# control_board_v2.net
KiCad netlist of a schematic drawn in EAGLE
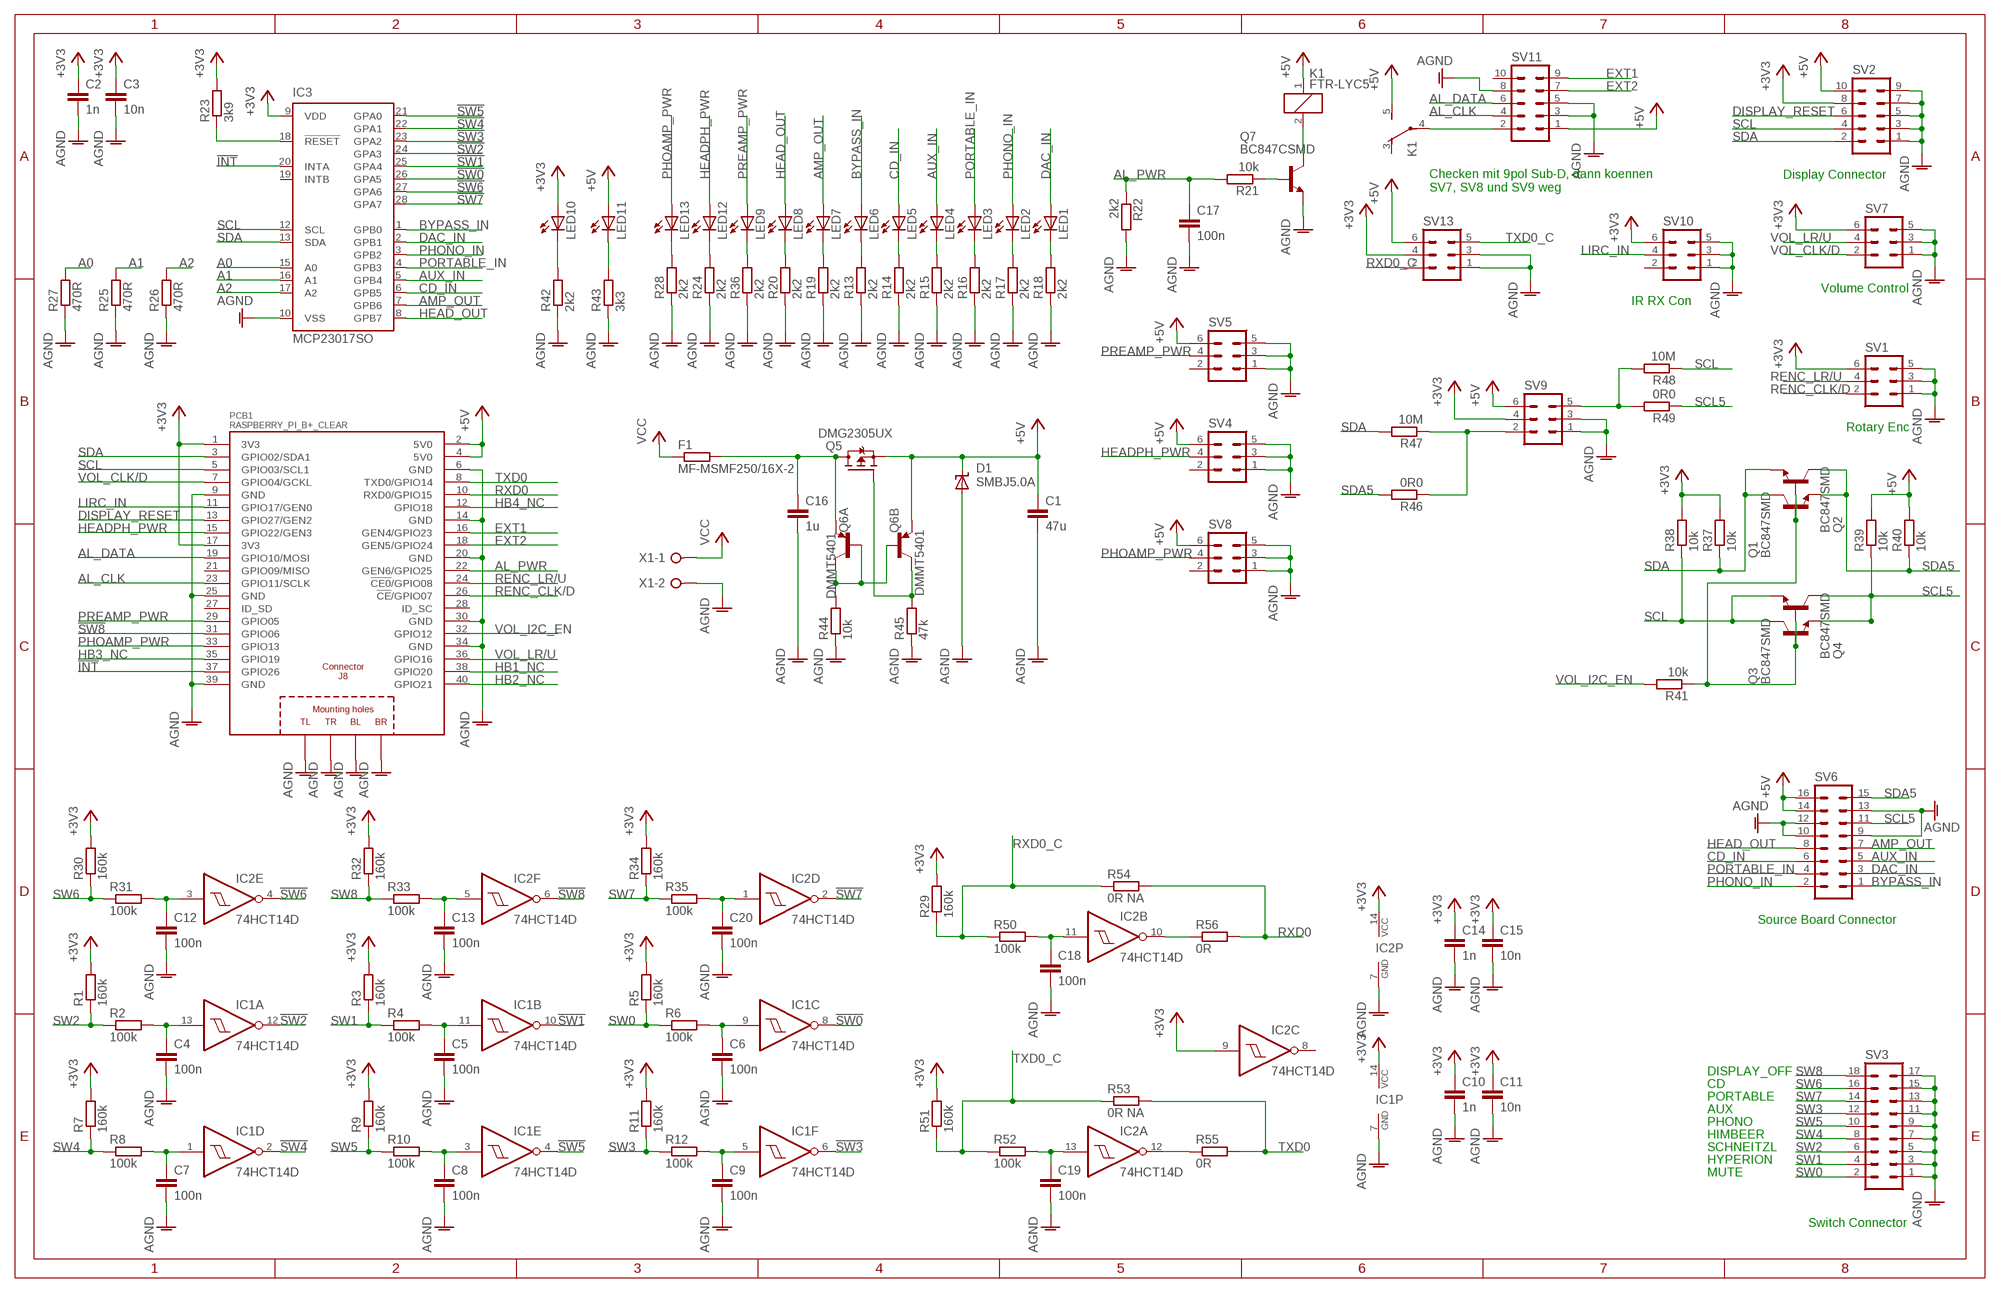
[diagram p0: schematic, sheet 1]

(export (version "E")
  (design (tool "Eeschema 10.0.6"))
  (components
    (comp (ref "C1")
      (value "47u")
      (footprint "eagle-import:C1812")
      (libsource (lib "eagle-import") (part "C-EUC1812"))
    )
    (comp (ref "C2")
      (value "1n")
      (footprint "eagle-import:C0603")
      (libsource (lib "eagle-import") (part "C-EUC0603"))
    )
    (comp (ref "C3")
      (value "10n")
      (footprint "eagle-import:C0603")
      (libsource (lib "eagle-import") (part "C-EUC0603"))
    )
    (comp (ref "C4")
      (value "100n")
      (footprint "eagle-import:C0603")
      (libsource (lib "eagle-import") (part "C-EUC0603"))
    )
    (comp (ref "C5")
      (value "100n")
      (footprint "eagle-import:C0603")
      (libsource (lib "eagle-import") (part "C-EUC0603"))
    )
    (comp (ref "C6")
      (value "100n")
      (footprint "eagle-import:C0603")
      (libsource (lib "eagle-import") (part "C-EUC0603"))
    )
    (comp (ref "C7")
      (value "100n")
      (footprint "eagle-import:C0603")
      (libsource (lib "eagle-import") (part "C-EUC0603"))
    )
    (comp (ref "C8")
      (value "100n")
      (footprint "eagle-import:C0603")
      (libsource (lib "eagle-import") (part "C-EUC0603"))
    )
    (comp (ref "C9")
      (value "100n")
      (footprint "eagle-import:C0603")
      (libsource (lib "eagle-import") (part "C-EUC0603"))
    )
    (comp (ref "C10")
      (value "1n")
      (footprint "eagle-import:C0603")
      (libsource (lib "eagle-import") (part "C-EUC0603"))
    )
    (comp (ref "C11")
      (value "10n")
      (footprint "eagle-import:C0603")
      (libsource (lib "eagle-import") (part "C-EUC0603"))
    )
    (comp (ref "C12")
      (value "100n")
      (footprint "eagle-import:C0603")
      (libsource (lib "eagle-import") (part "C-EUC0603"))
    )
    (comp (ref "C13")
      (value "100n")
      (footprint "eagle-import:C0603")
      (libsource (lib "eagle-import") (part "C-EUC0603"))
    )
    (comp (ref "C14")
      (value "1n")
      (footprint "eagle-import:C0603")
      (libsource (lib "eagle-import") (part "C-EUC0603"))
    )
    (comp (ref "C15")
      (value "10n")
      (footprint "eagle-import:C0603")
      (libsource (lib "eagle-import") (part "C-EUC0603"))
    )
    (comp (ref "C16")
      (value "1u")
      (footprint "eagle-import:C1206")
      (libsource (lib "eagle-import") (part "C-EUC1206"))
    )
    (comp (ref "C17")
      (value "100n")
      (footprint "eagle-import:C0603")
      (libsource (lib "eagle-import") (part "C-EUC0603"))
    )
    (comp (ref "C18")
      (value "100n")
      (footprint "eagle-import:C0603")
      (libsource (lib "eagle-import") (part "C-EUC0603"))
    )
    (comp (ref "C19")
      (value "100n")
      (footprint "eagle-import:C0603")
      (libsource (lib "eagle-import") (part "C-EUC0603"))
    )
    (comp (ref "C20")
      (value "100n")
      (footprint "eagle-import:C0603")
      (libsource (lib "eagle-import") (part "C-EUC0603"))
    )
    (comp (ref "D1")
      (value "SMBJ5.0A")
      (footprint "eagle-import:SMBJ")
      (libsource (lib "eagle-import") (part "SMBJ5.0A"))
    )
    (comp (ref "F1")
      (value "MF-MSMF250/16X-2")
      (footprint "eagle-import:1812X7R")
      (libsource (lib "eagle-import") (part "R-EU_1812X7R"))
    )
    (comp (ref "IC1")
      (value "74HCT14D")
      (footprint "eagle-import:SO14")
      (libsource (lib "eagle-import") (part "7414DHCT"))
    )
    (comp (ref "IC2")
      (value "74HCT14D")
      (footprint "eagle-import:SO14")
      (libsource (lib "eagle-import") (part "7414DHCT"))
    )
    (comp (ref "IC3")
      (value "MCP23017SO")
      (footprint "eagle-import:SO28W")
      (fields (field (name "MF") "MICROCHIP") (field (name "MPN") "MCP23017-E/SO"))
      (libsource (lib "eagle-import") (part "MCP23017SO"))
    )
    (comp (ref "K1")
      (value "FTR-LYC5")
      (footprint "eagle-import:FTR-LYC")
      (libsource (lib "eagle-import") (part "FTR-LYC5"))
    )
    (comp (ref "LED1")
      (value "LEDCHIPLED_0603")
      (footprint "eagle-import:CHIPLED_0603")
      (libsource (lib "eagle-import") (part "LEDCHIPLED_0603"))
    )
    (comp (ref "LED2")
      (value "LEDCHIPLED_0603")
      (footprint "eagle-import:CHIPLED_0603")
      (libsource (lib "eagle-import") (part "LEDCHIPLED_0603"))
    )
    (comp (ref "LED3")
      (value "LEDCHIPLED_0603")
      (footprint "eagle-import:CHIPLED_0603")
      (libsource (lib "eagle-import") (part "LEDCHIPLED_0603"))
    )
    (comp (ref "LED4")
      (value "LEDCHIPLED_0603")
      (footprint "eagle-import:CHIPLED_0603")
      (libsource (lib "eagle-import") (part "LEDCHIPLED_0603"))
    )
    (comp (ref "LED5")
      (value "LEDCHIPLED_0603")
      (footprint "eagle-import:CHIPLED_0603")
      (libsource (lib "eagle-import") (part "LEDCHIPLED_0603"))
    )
    (comp (ref "LED6")
      (value "LEDCHIPLED_0603")
      (footprint "eagle-import:CHIPLED_0603")
      (libsource (lib "eagle-import") (part "LEDCHIPLED_0603"))
    )
    (comp (ref "LED7")
      (value "LEDCHIPLED_0603")
      (footprint "eagle-import:CHIPLED_0603")
      (libsource (lib "eagle-import") (part "LEDCHIPLED_0603"))
    )
    (comp (ref "LED8")
      (value "LEDCHIPLED_0603")
      (footprint "eagle-import:CHIPLED_0603")
      (libsource (lib "eagle-import") (part "LEDCHIPLED_0603"))
    )
    (comp (ref "LED9")
      (value "LEDCHIPLED_0603")
      (footprint "eagle-import:CHIPLED_0603")
      (libsource (lib "eagle-import") (part "LEDCHIPLED_0603"))
    )
    (comp (ref "LED10")
      (value "LEDCHIPLED_0603")
      (footprint "eagle-import:CHIPLED_0603")
      (libsource (lib "eagle-import") (part "LEDCHIPLED_0603"))
    )
    (comp (ref "LED11")
      (value "LEDCHIPLED_0603")
      (footprint "eagle-import:CHIPLED_0603")
      (libsource (lib "eagle-import") (part "LEDCHIPLED_0603"))
    )
    (comp (ref "LED12")
      (value "LEDCHIPLED_0603")
      (footprint "eagle-import:CHIPLED_0603")
      (libsource (lib "eagle-import") (part "LEDCHIPLED_0603"))
    )
    (comp (ref "LED13")
      (value "LEDCHIPLED_0603")
      (footprint "eagle-import:CHIPLED_0603")
      (libsource (lib "eagle-import") (part "LEDCHIPLED_0603"))
    )
    (comp (ref "PCB1")
      (value "RASPBERRY_PI_B+_CLEAR")
      (footprint "eagle-import:RASPBERRY_PI_PLUS_CLEAR")
      (libsource (lib "eagle-import") (part "RASPBERRY_PI_B+_CLEAR"))
    )
    (comp (ref "Q1")
      (value "BC847SMD")
      (footprint "eagle-import:SOT23")
      (libsource (lib "eagle-import") (part "BC847SMD"))
    )
    (comp (ref "Q2")
      (value "BC847SMD")
      (footprint "eagle-import:SOT23")
      (libsource (lib "eagle-import") (part "BC847SMD"))
    )
    (comp (ref "Q3")
      (value "BC847SMD")
      (footprint "eagle-import:SOT23")
      (libsource (lib "eagle-import") (part "BC847SMD"))
    )
    (comp (ref "Q4")
      (value "BC847SMD")
      (footprint "eagle-import:SOT23")
      (libsource (lib "eagle-import") (part "BC847SMD"))
    )
    (comp (ref "Q5")
      (value "DMG2305UX")
      (footprint "eagle-import:SOT23")
      (libsource (lib "eagle-import") (part "DMG2305UX"))
    )
    (comp (ref "Q6")
      (value "DMMT5401")
      (footprint "eagle-import:SOT23-6")
      (libsource (lib "eagle-import") (part "DMMT5401"))
    )
    (comp (ref "Q7")
      (value "BC847CSMD")
      (footprint "eagle-import:SOT23")
      (libsource (lib "eagle-import") (part "BC847SMDC"))
    )
    (comp (ref "R1")
      (value "160k")
      (footprint "eagle-import:R0603")
      (libsource (lib "eagle-import") (part "R-EU_R0603"))
    )
    (comp (ref "R2")
      (value "100k")
      (footprint "eagle-import:R0603")
      (libsource (lib "eagle-import") (part "R-EU_R0603"))
    )
    (comp (ref "R3")
      (value "160k")
      (footprint "eagle-import:R0603")
      (libsource (lib "eagle-import") (part "R-EU_R0603"))
    )
    (comp (ref "R4")
      (value "100k")
      (footprint "eagle-import:R0603")
      (libsource (lib "eagle-import") (part "R-EU_R0603"))
    )
    (comp (ref "R5")
      (value "160k")
      (footprint "eagle-import:R0603")
      (libsource (lib "eagle-import") (part "R-EU_R0603"))
    )
    (comp (ref "R6")
      (value "100k")
      (footprint "eagle-import:R0603")
      (libsource (lib "eagle-import") (part "R-EU_R0603"))
    )
    (comp (ref "R7")
      (value "160k")
      (footprint "eagle-import:R0603")
      (libsource (lib "eagle-import") (part "R-EU_R0603"))
    )
    (comp (ref "R8")
      (value "100k")
      (footprint "eagle-import:R0603")
      (libsource (lib "eagle-import") (part "R-EU_R0603"))
    )
    (comp (ref "R9")
      (value "160k")
      (footprint "eagle-import:R0603")
      (libsource (lib "eagle-import") (part "R-EU_R0603"))
    )
    (comp (ref "R10")
      (value "100k")
      (footprint "eagle-import:R0603")
      (libsource (lib "eagle-import") (part "R-EU_R0603"))
    )
    (comp (ref "R11")
      (value "160k")
      (footprint "eagle-import:R0603")
      (libsource (lib "eagle-import") (part "R-EU_R0603"))
    )
    (comp (ref "R12")
      (value "100k")
      (footprint "eagle-import:R0603")
      (libsource (lib "eagle-import") (part "R-EU_R0603"))
    )
    (comp (ref "R13")
      (value "2k2")
      (footprint "eagle-import:R0603")
      (libsource (lib "eagle-import") (part "R-EU_R0603"))
    )
    (comp (ref "R14")
      (value "2k2")
      (footprint "eagle-import:R0603")
      (libsource (lib "eagle-import") (part "R-EU_R0603"))
    )
    (comp (ref "R15")
      (value "2k2")
      (footprint "eagle-import:R0603")
      (libsource (lib "eagle-import") (part "R-EU_R0603"))
    )
    (comp (ref "R16")
      (value "2k2")
      (footprint "eagle-import:R0603")
      (libsource (lib "eagle-import") (part "R-EU_R0603"))
    )
    (comp (ref "R17")
      (value "2k2")
      (footprint "eagle-import:R0603")
      (libsource (lib "eagle-import") (part "R-EU_R0603"))
    )
    (comp (ref "R18")
      (value "2k2")
      (footprint "eagle-import:R0603")
      (libsource (lib "eagle-import") (part "R-EU_R0603"))
    )
    (comp (ref "R19")
      (value "2k2")
      (footprint "eagle-import:R0603")
      (libsource (lib "eagle-import") (part "R-EU_R0603"))
    )
    (comp (ref "R20")
      (value "2k2")
      (footprint "eagle-import:R0603")
      (libsource (lib "eagle-import") (part "R-EU_R0603"))
    )
    (comp (ref "R21")
      (value "10k")
      (footprint "eagle-import:R0603")
      (libsource (lib "eagle-import") (part "R-EU_R0603"))
    )
    (comp (ref "R22")
      (value "2k2")
      (footprint "eagle-import:R0603")
      (libsource (lib "eagle-import") (part "R-EU_R0603"))
    )
    (comp (ref "R23")
      (value "3k9")
      (footprint "eagle-import:R1206")
      (libsource (lib "eagle-import") (part "R-EU_R1206"))
    )
    (comp (ref "R24")
      (value "2k2")
      (footprint "eagle-import:R0603")
      (libsource (lib "eagle-import") (part "R-EU_R0603"))
    )
    (comp (ref "R25")
      (value "470R")
      (footprint "eagle-import:R0603")
      (libsource (lib "eagle-import") (part "R-EU_R0603"))
    )
    (comp (ref "R26")
      (value "470R")
      (footprint "eagle-import:R0603")
      (libsource (lib "eagle-import") (part "R-EU_R0603"))
    )
    (comp (ref "R27")
      (value "470R")
      (footprint "eagle-import:R0603")
      (libsource (lib "eagle-import") (part "R-EU_R0603"))
    )
    (comp (ref "R28")
      (value "2k2")
      (footprint "eagle-import:R0603")
      (libsource (lib "eagle-import") (part "R-EU_R0603"))
    )
    (comp (ref "R29")
      (value "160k")
      (footprint "eagle-import:R0603")
      (libsource (lib "eagle-import") (part "R-EU_R0603"))
    )
    (comp (ref "R30")
      (value "160k")
      (footprint "eagle-import:R0603")
      (libsource (lib "eagle-import") (part "R-EU_R0603"))
    )
    (comp (ref "R31")
      (value "100k")
      (footprint "eagle-import:R0603")
      (libsource (lib "eagle-import") (part "R-EU_R0603"))
    )
    (comp (ref "R32")
      (value "160k")
      (footprint "eagle-import:R0603")
      (libsource (lib "eagle-import") (part "R-EU_R0603"))
    )
    (comp (ref "R33")
      (value "100k")
      (footprint "eagle-import:R0603")
      (libsource (lib "eagle-import") (part "R-EU_R0603"))
    )
    (comp (ref "R34")
      (value "160k")
      (footprint "eagle-import:R0603")
      (libsource (lib "eagle-import") (part "R-EU_R0603"))
    )
    (comp (ref "R35")
      (value "100k")
      (footprint "eagle-import:R0603")
      (libsource (lib "eagle-import") (part "R-EU_R0603"))
    )
    (comp (ref "R36")
      (value "2k2")
      (footprint "eagle-import:R0603")
      (libsource (lib "eagle-import") (part "R-EU_R0603"))
    )
    (comp (ref "R37")
      (value "10k")
      (footprint "eagle-import:R1206")
      (libsource (lib "eagle-import") (part "resistor_R-EU_R1206"))
    )
    (comp (ref "R38")
      (value "10k")
      (footprint "eagle-import:R0603")
      (libsource (lib "eagle-import") (part "resistor_R-EU_R0603"))
    )
    (comp (ref "R39")
      (value "10k")
      (footprint "eagle-import:R0603")
      (libsource (lib "eagle-import") (part "resistor_R-EU_R0603"))
    )
    (comp (ref "R40")
      (value "10k")
      (footprint "eagle-import:R0603")
      (libsource (lib "eagle-import") (part "R-EU_R0603"))
    )
    (comp (ref "R41")
      (value "10k")
      (footprint "eagle-import:R1206")
      (libsource (lib "eagle-import") (part "resistor_R-EU_R1206"))
    )
    (comp (ref "R42")
      (value "2k2")
      (footprint "eagle-import:R0603")
      (libsource (lib "eagle-import") (part "R-EU_R0603"))
    )
    (comp (ref "R43")
      (value "3k3")
      (footprint "eagle-import:R0603")
      (libsource (lib "eagle-import") (part "R-EU_R0603"))
    )
    (comp (ref "R44")
      (value "10k")
      (footprint "eagle-import:R0603")
      (libsource (lib "eagle-import") (part "R-EU_R0603"))
    )
    (comp (ref "R45")
      (value "47k")
      (footprint "eagle-import:R0603")
      (libsource (lib "eagle-import") (part "R-EU_R0603"))
    )
    (comp (ref "R46")
      (value "0R0")
      (footprint "eagle-import:R0603")
      (libsource (lib "eagle-import") (part "R-EU_R0603"))
    )
    (comp (ref "R47")
      (value "10M")
      (footprint "eagle-import:R0603")
      (libsource (lib "eagle-import") (part "R-EU_R0603"))
    )
    (comp (ref "R48")
      (value "10M")
      (footprint "eagle-import:R0603")
      (libsource (lib "eagle-import") (part "R-EU_R0603"))
    )
    (comp (ref "R49")
      (value "0R0")
      (footprint "eagle-import:R0603")
      (libsource (lib "eagle-import") (part "R-EU_R0603"))
    )
    (comp (ref "R50")
      (value "100k")
      (footprint "eagle-import:R0603")
      (libsource (lib "eagle-import") (part "R-EU_R0603"))
    )
    (comp (ref "R51")
      (value "160k")
      (footprint "eagle-import:R0603")
      (libsource (lib "eagle-import") (part "R-EU_R0603"))
    )
    (comp (ref "R52")
      (value "100k")
      (footprint "eagle-import:R0603")
      (libsource (lib "eagle-import") (part "R-EU_R0603"))
    )
    (comp (ref "R53")
      (value "0R NA")
      (footprint "eagle-import:R0603")
      (libsource (lib "eagle-import") (part "R-EU_R0603"))
    )
    (comp (ref "R54")
      (value "0R NA")
      (footprint "eagle-import:R0603")
      (libsource (lib "eagle-import") (part "R-EU_R0603"))
    )
    (comp (ref "R55")
      (value "0R")
      (footprint "eagle-import:R0603")
      (libsource (lib "eagle-import") (part "R-EU_R0603"))
    )
    (comp (ref "R56")
      (value "0R")
      (footprint "eagle-import:R0603")
      (libsource (lib "eagle-import") (part "R-EU_R0603"))
    )
    (comp (ref "SV1")
      (value "MA03-2B")
      (footprint "eagle-import:MA03-2_BORDER")
      (libsource (lib "eagle-import") (part "MA03-2B"))
    )
    (comp (ref "SV2")
      (value "MA05-2B")
      (footprint "eagle-import:MA05-2_BORDER")
      (libsource (lib "eagle-import") (part "MA05-2B"))
    )
    (comp (ref "SV3")
      (value "MA09-2B")
      (footprint "eagle-import:MA09-2_BORDER")
      (libsource (lib "eagle-import") (part "MA09-2B"))
    )
    (comp (ref "SV4")
      (value "MA03-2B")
      (footprint "eagle-import:MA03-2_BORDER")
      (libsource (lib "eagle-import") (part "MA03-2B"))
    )
    (comp (ref "SV5")
      (value "MA03-2B")
      (footprint "eagle-import:MA03-2_BORDER")
      (libsource (lib "eagle-import") (part "MA03-2B"))
    )
    (comp (ref "SV6")
      (value "MA08-2B")
      (footprint "eagle-import:MA08-2_BORDER")
      (libsource (lib "eagle-import") (part "MA08-2B"))
    )
    (comp (ref "SV7")
      (value "MA03-2B")
      (footprint "eagle-import:MA03-2_BORDER")
      (libsource (lib "eagle-import") (part "MA03-2B"))
    )
    (comp (ref "SV8")
      (value "MA03-2B")
      (footprint "eagle-import:MA03-2_BORDER")
      (libsource (lib "eagle-import") (part "MA03-2B"))
    )
    (comp (ref "SV9")
      (value "MA03-2B")
      (footprint "eagle-import:MA03-2_BORDER")
      (libsource (lib "eagle-import") (part "MA03-2B"))
    )
    (comp (ref "SV10")
      (value "MA03-2B")
      (footprint "eagle-import:MA03-2_BORDER")
      (libsource (lib "eagle-import") (part "MA03-2B"))
    )
    (comp (ref "SV11")
      (value "MA05-2B")
      (footprint "eagle-import:MA05-2_BORDER")
      (libsource (lib "eagle-import") (part "MA05-2B"))
    )
    (comp (ref "SV13")
      (value "MA03-2B")
      (footprint "eagle-import:MA03-2_BORDER")
      (libsource (lib "eagle-import") (part "MA03-2B"))
    )
    (comp (ref "X1")
      (value "W237-02P")
      (footprint "eagle-import:W237-132")
      (libsource (lib "eagle-import") (part "W237-02P"))
    )
  )
  (nets
    (net (code "1") (name "+3V3") (class "Default")
      (node (ref "C10") (pin "1") (pinfunction "1_1") (pintype "passive"))
      (node (ref "C11") (pin "1") (pinfunction "1_1") (pintype "passive"))
      (node (ref "C14") (pin "1") (pinfunction "1_1") (pintype "passive"))
      (node (ref "C15") (pin "1") (pinfunction "1_1") (pintype "passive"))
      (node (ref "C2") (pin "1") (pinfunction "1_1") (pintype "passive"))
      (node (ref "C3") (pin "1") (pinfunction "1_1") (pintype "passive"))
      (node (ref "IC1") (pin "14") (pinfunction "VCC_14") (pintype "power_in"))
      (node (ref "IC2") (pin "14") (pinfunction "VCC_14") (pintype "power_in"))
      (node (ref "IC2") (pin "9") (pinfunction "I_9") (pintype "input"))
      (node (ref "IC3") (pin "9") (pinfunction "VDD_9") (pintype "power_in"))
      (node (ref "LED10") (pin "A") (pinfunction "A_A") (pintype "passive"))
      (node (ref "PCB1") (pin "1") (pinfunction "3V3_1") (pintype "power_in"))
      (node (ref "PCB1") (pin "17") (pinfunction "3V3_17") (pintype "power_in"))
      (node (ref "R1") (pin "2") (pinfunction "2_2") (pintype "passive"))
      (node (ref "R11") (pin "2") (pinfunction "2_2") (pintype "passive"))
      (node (ref "R23") (pin "2") (pinfunction "2_2") (pintype "passive"))
      (node (ref "R29") (pin "2") (pinfunction "2_2") (pintype "passive"))
      (node (ref "R3") (pin "2") (pinfunction "2_2") (pintype "passive"))
      (node (ref "R30") (pin "2") (pinfunction "2_2") (pintype "passive"))
      (node (ref "R32") (pin "2") (pinfunction "2_2") (pintype "passive"))
      (node (ref "R34") (pin "2") (pinfunction "2_2") (pintype "passive"))
      (node (ref "R37") (pin "2") (pinfunction "2_2") (pintype "passive"))
      (node (ref "R38") (pin "2") (pinfunction "2_2") (pintype "passive"))
      (node (ref "R5") (pin "2") (pinfunction "2_2") (pintype "passive"))
      (node (ref "R51") (pin "2") (pinfunction "2_2") (pintype "passive"))
      (node (ref "R7") (pin "2") (pinfunction "2_2") (pintype "passive"))
      (node (ref "R9") (pin "2") (pinfunction "2_2") (pintype "passive"))
      (node (ref "SV1") (pin "6") (pinfunction "6_6") (pintype "passive"))
      (node (ref "SV10") (pin "6") (pinfunction "6_6") (pintype "passive"))
      (node (ref "SV13") (pin "4") (pinfunction "4_4") (pintype "passive"))
      (node (ref "SV2") (pin "8") (pinfunction "8_8") (pintype "passive"))
      (node (ref "SV7") (pin "6") (pinfunction "6_6") (pintype "passive"))
      (node (ref "SV9") (pin "4") (pinfunction "4_4") (pintype "passive"))
    )
    (net (code "2") (name "+5V") (class "Default")
      (node (ref "C1") (pin "1") (pinfunction "1_1") (pintype "passive"))
      (node (ref "D1") (pin "C") (pinfunction "C_C") (pintype "passive"))
      (node (ref "K1") (pin "1") (pinfunction "1_1") (pintype "passive"))
      (node (ref "K1") (pin "5") (pinfunction "S_5") (pintype "passive"))
      (node (ref "LED11") (pin "A") (pinfunction "A_A") (pintype "passive"))
      (node (ref "PCB1") (pin "2") (pinfunction "5V0_2") (pintype "power_in"))
      (node (ref "PCB1") (pin "4") (pinfunction "5V0_4") (pintype "power_in"))
      (node (ref "Q5") (pin "2") (pinfunction "S_2") (pintype "passive"))
      (node (ref "Q6") (pin "5") (pinfunction "E_5") (pintype "passive"))
      (node (ref "R39") (pin "2") (pinfunction "2_2") (pintype "passive"))
      (node (ref "R40") (pin "2") (pinfunction "2_2") (pintype "passive"))
      (node (ref "SV11") (pin "1") (pinfunction "1_1") (pintype "passive"))
      (node (ref "SV13") (pin "6") (pinfunction "6_6") (pintype "passive"))
      (node (ref "SV2") (pin "10") (pinfunction "10_10") (pintype "passive"))
      (node (ref "SV4") (pin "6") (pinfunction "6_6") (pintype "passive"))
      (node (ref "SV5") (pin "6") (pinfunction "6_6") (pintype "passive"))
      (node (ref "SV6") (pin "14") (pinfunction "14_14") (pintype "passive"))
      (node (ref "SV6") (pin "16") (pinfunction "16_16") (pintype "passive"))
      (node (ref "SV8") (pin "6") (pinfunction "6_6") (pintype "passive"))
      (node (ref "SV9") (pin "6") (pinfunction "6_6") (pintype "passive"))
    )
    (net (code "3") (name "/A0") (class "Default")
      (node (ref "IC3") (pin "15") (pinfunction "A0_15") (pintype "input"))
      (node (ref "R27") (pin "2") (pinfunction "2_2") (pintype "passive"))
    )
    (net (code "4") (name "/A1") (class "Default")
      (node (ref "IC3") (pin "16") (pinfunction "A1_16") (pintype "input"))
      (node (ref "R25") (pin "2") (pinfunction "2_2") (pintype "passive"))
    )
    (net (code "5") (name "/A2") (class "Default")
      (node (ref "IC3") (pin "17") (pinfunction "A2_17") (pintype "input"))
      (node (ref "R26") (pin "2") (pinfunction "2_2") (pintype "passive"))
    )
    (net (code "6") (name "/AL_CLK") (class "Default")
      (node (ref "PCB1") (pin "23") (pinfunction "GPIO11/SCLK_23") (pintype "bidirectional"))
      (node (ref "SV11") (pin "4") (pinfunction "4_4") (pintype "passive"))
    )
    (net (code "7") (name "/AL_DATA") (class "Default")
      (node (ref "PCB1") (pin "19") (pinfunction "GPIO10/MOSI_19") (pintype "bidirectional"))
      (node (ref "SV11") (pin "6") (pinfunction "6_6") (pintype "passive"))
    )
    (net (code "8") (name "/AL_PWR") (class "Default")
      (node (ref "C17") (pin "1") (pinfunction "1_1") (pintype "passive"))
      (node (ref "PCB1") (pin "22") (pinfunction "GEN6/GPIO25_22") (pintype "bidirectional"))
      (node (ref "R21") (pin "2") (pinfunction "2_2") (pintype "passive"))
      (node (ref "R22") (pin "1") (pinfunction "1_1") (pintype "passive"))
    )
    (net (code "9") (name "/AMP_OUT") (class "Default")
      (node (ref "IC3") (pin "7") (pinfunction "GPB6_7") (pintype "bidirectional"))
      (node (ref "LED7") (pin "A") (pinfunction "A_A") (pintype "passive"))
      (node (ref "SV6") (pin "7") (pinfunction "7_7") (pintype "passive"))
    )
    (net (code "10") (name "/AUX_IN") (class "Default")
      (node (ref "IC3") (pin "5") (pinfunction "GPB4_5") (pintype "bidirectional"))
      (node (ref "LED4") (pin "A") (pinfunction "A_A") (pintype "passive"))
      (node (ref "SV6") (pin "5") (pinfunction "5_5") (pintype "passive"))
    )
    (net (code "11") (name "/BYPASS_IN") (class "Default")
      (node (ref "IC3") (pin "1") (pinfunction "GPB0_1") (pintype "bidirectional"))
      (node (ref "LED6") (pin "A") (pinfunction "A_A") (pintype "passive"))
      (node (ref "SV6") (pin "1") (pinfunction "1_1") (pintype "passive"))
    )
    (net (code "12") (name "/CD_IN") (class "Default")
      (node (ref "IC3") (pin "6") (pinfunction "GPB5_6") (pintype "bidirectional"))
      (node (ref "LED5") (pin "A") (pinfunction "A_A") (pintype "passive"))
      (node (ref "SV6") (pin "6") (pinfunction "6_6") (pintype "passive"))
    )
    (net (code "13") (name "/DAC_IN") (class "Default")
      (node (ref "IC3") (pin "2") (pinfunction "GPB1_2") (pintype "bidirectional"))
      (node (ref "LED1") (pin "A") (pinfunction "A_A") (pintype "passive"))
      (node (ref "SV6") (pin "3") (pinfunction "3_3") (pintype "passive"))
    )
    (net (code "14") (name "/DISPLAY_RESET") (class "Default")
      (node (ref "PCB1") (pin "13") (pinfunction "GPIO27/GEN2_13") (pintype "bidirectional"))
      (node (ref "SV2") (pin "6") (pinfunction "6_6") (pintype "passive"))
    )
    (net (code "15") (name "/EXT1") (class "Default")
      (node (ref "PCB1") (pin "16") (pinfunction "GEN4/GPIO23_16") (pintype "bidirectional"))
      (node (ref "SV11") (pin "9") (pinfunction "9_9") (pintype "passive"))
    )
    (net (code "16") (name "/EXT2") (class "Default")
      (node (ref "PCB1") (pin "18") (pinfunction "GEN5/GPIO24_18") (pintype "bidirectional"))
      (node (ref "SV11") (pin "7") (pinfunction "7_7") (pintype "passive"))
    )
    (net (code "17") (name "/HB1_NC") (class "Default")
      (node (ref "PCB1") (pin "38") (pinfunction "GPIO20_38") (pintype "bidirectional"))
    )
    (net (code "18") (name "/HB2_NC") (class "Default")
      (node (ref "PCB1") (pin "40") (pinfunction "GPIO21_40") (pintype "bidirectional"))
    )
    (net (code "19") (name "/HB3_NC") (class "Default")
      (node (ref "PCB1") (pin "35") (pinfunction "GPIO19_35") (pintype "bidirectional"))
    )
    (net (code "20") (name "/HB4_NC") (class "Default")
      (node (ref "PCB1") (pin "12") (pinfunction "GPIO18_12") (pintype "bidirectional"))
    )
    (net (code "21") (name "/HEADPH_PWR") (class "Default")
      (node (ref "LED12") (pin "A") (pinfunction "A_A") (pintype "passive"))
      (node (ref "PCB1") (pin "15") (pinfunction "GPIO22/GEN3_15") (pintype "bidirectional"))
      (node (ref "SV4") (pin "4") (pinfunction "4_4") (pintype "passive"))
    )
    (net (code "22") (name "/HEAD_OUT") (class "Default")
      (node (ref "IC3") (pin "8") (pinfunction "GPB7_8") (pintype "bidirectional"))
      (node (ref "LED8") (pin "A") (pinfunction "A_A") (pintype "passive"))
      (node (ref "SV6") (pin "8") (pinfunction "8_8") (pintype "passive"))
    )
    (net (code "23") (name "/LIRC_IN") (class "Default")
      (node (ref "PCB1") (pin "11") (pinfunction "GPIO17/GEN0_11") (pintype "bidirectional"))
      (node (ref "SV10") (pin "4") (pinfunction "4_4") (pintype "passive"))
    )
    (net (code "24") (name "/PHOAMP_PWR") (class "Default")
      (node (ref "LED13") (pin "A") (pinfunction "A_A") (pintype "passive"))
      (node (ref "PCB1") (pin "33") (pinfunction "GPIO13_33") (pintype "bidirectional"))
      (node (ref "SV8") (pin "4") (pinfunction "4_4") (pintype "passive"))
    )
    (net (code "25") (name "/PHONO_IN") (class "Default")
      (node (ref "IC3") (pin "3") (pinfunction "GPB2_3") (pintype "bidirectional"))
      (node (ref "LED2") (pin "A") (pinfunction "A_A") (pintype "passive"))
      (node (ref "SV6") (pin "2") (pinfunction "2_2") (pintype "passive"))
    )
    (net (code "26") (name "/PORTABLE_IN") (class "Default")
      (node (ref "IC3") (pin "4") (pinfunction "GPB3_4") (pintype "bidirectional"))
      (node (ref "LED3") (pin "A") (pinfunction "A_A") (pintype "passive"))
      (node (ref "SV6") (pin "4") (pinfunction "4_4") (pintype "passive"))
    )
    (net (code "27") (name "/PREAMP_PWR") (class "Default")
      (node (ref "LED9") (pin "A") (pinfunction "A_A") (pintype "passive"))
      (node (ref "PCB1") (pin "29") (pinfunction "GPIO05_29") (pintype "bidirectional"))
      (node (ref "SV5") (pin "4") (pinfunction "4_4") (pintype "passive"))
    )
    (net (code "28") (name "/RENC_CLK{slash}D") (class "Default")
      (node (ref "PCB1") (pin "26") (pinfunction "~{CE}/GPIO07_26") (pintype "bidirectional"))
      (node (ref "SV1") (pin "2") (pinfunction "2_2") (pintype "passive"))
    )
    (net (code "29") (name "/RENC_LR{slash}U") (class "Default")
      (node (ref "PCB1") (pin "24") (pinfunction "~{CE0}/GPIO08_24") (pintype "bidirectional"))
      (node (ref "SV1") (pin "4") (pinfunction "4_4") (pintype "passive"))
    )
    (net (code "30") (name "/RXD0") (class "Default")
      (node (ref "PCB1") (pin "10") (pinfunction "RXD0/GPIO15_10") (pintype "bidirectional"))
      (node (ref "R54") (pin "2") (pinfunction "2_2") (pintype "passive"))
      (node (ref "R56") (pin "2") (pinfunction "2_2") (pintype "passive"))
    )
    (net (code "31") (name "/RXD0_C") (class "Default")
      (node (ref "R29") (pin "1") (pinfunction "1_1") (pintype "passive"))
      (node (ref "R50") (pin "1") (pinfunction "1_1") (pintype "passive"))
      (node (ref "R54") (pin "1") (pinfunction "1_1") (pintype "passive"))
      (node (ref "SV13") (pin "2") (pinfunction "2_2") (pintype "passive"))
    )
    (net (code "32") (name "/SCL") (class "Default")
      (node (ref "IC3") (pin "12") (pinfunction "SCL_12") (pintype "input"))
      (node (ref "PCB1") (pin "5") (pinfunction "GPIO03/SCL1_5") (pintype "bidirectional"))
      (node (ref "Q3") (pin "3") (pinfunction "C_3") (pintype "passive"))
      (node (ref "Q4") (pin "2") (pinfunction "E_2") (pintype "passive"))
      (node (ref "R38") (pin "1") (pinfunction "1_1") (pintype "passive"))
      (node (ref "R48") (pin "1") (pinfunction "1_1") (pintype "passive"))
      (node (ref "SV2") (pin "4") (pinfunction "4_4") (pintype "passive"))
    )
    (net (code "33") (name "/SCL5") (class "Default")
      (node (ref "Q3") (pin "2") (pinfunction "E_2") (pintype "passive"))
      (node (ref "Q4") (pin "3") (pinfunction "C_3") (pintype "passive"))
      (node (ref "R39") (pin "1") (pinfunction "1_1") (pintype "passive"))
      (node (ref "R49") (pin "1") (pinfunction "1_1") (pintype "passive"))
      (node (ref "SV6") (pin "11") (pinfunction "11_11") (pintype "passive"))
    )
    (net (code "34") (name "/SDA") (class "Default")
      (node (ref "IC3") (pin "13") (pinfunction "SDA_13") (pintype "bidirectional"))
      (node (ref "PCB1") (pin "3") (pinfunction "GPIO02/SDA1_3") (pintype "bidirectional"))
      (node (ref "Q1") (pin "3") (pinfunction "C_3") (pintype "passive"))
      (node (ref "Q2") (pin "2") (pinfunction "E_2") (pintype "passive"))
      (node (ref "R37") (pin "1") (pinfunction "1_1") (pintype "passive"))
      (node (ref "R47") (pin "2") (pinfunction "2_2") (pintype "passive"))
      (node (ref "SV2") (pin "2") (pinfunction "2_2") (pintype "passive"))
    )
    (net (code "35") (name "/SDA5") (class "Default")
      (node (ref "Q1") (pin "2") (pinfunction "E_2") (pintype "passive"))
      (node (ref "Q2") (pin "3") (pinfunction "C_3") (pintype "passive"))
      (node (ref "R40") (pin "1") (pinfunction "1_1") (pintype "passive"))
      (node (ref "R46") (pin "2") (pinfunction "2_2") (pintype "passive"))
      (node (ref "SV6") (pin "15") (pinfunction "15_15") (pintype "passive"))
    )
    (net (code "36") (name "/SW0") (class "Default")
      (node (ref "R5") (pin "1") (pinfunction "1_1") (pintype "passive"))
      (node (ref "R6") (pin "1") (pinfunction "1_1") (pintype "passive"))
      (node (ref "SV3") (pin "2") (pinfunction "2_2") (pintype "passive"))
    )
    (net (code "37") (name "/SW1") (class "Default")
      (node (ref "R3") (pin "1") (pinfunction "1_1") (pintype "passive"))
      (node (ref "R4") (pin "1") (pinfunction "1_1") (pintype "passive"))
      (node (ref "SV3") (pin "4") (pinfunction "4_4") (pintype "passive"))
    )
    (net (code "38") (name "/SW2") (class "Default")
      (node (ref "R1") (pin "1") (pinfunction "1_1") (pintype "passive"))
      (node (ref "R2") (pin "1") (pinfunction "1_1") (pintype "passive"))
      (node (ref "SV3") (pin "6") (pinfunction "6_6") (pintype "passive"))
    )
    (net (code "39") (name "/SW3") (class "Default")
      (node (ref "R11") (pin "1") (pinfunction "1_1") (pintype "passive"))
      (node (ref "R12") (pin "1") (pinfunction "1_1") (pintype "passive"))
      (node (ref "SV3") (pin "12") (pinfunction "12_12") (pintype "passive"))
    )
    (net (code "40") (name "/SW4") (class "Default")
      (node (ref "R7") (pin "1") (pinfunction "1_1") (pintype "passive"))
      (node (ref "R8") (pin "1") (pinfunction "1_1") (pintype "passive"))
      (node (ref "SV3") (pin "8") (pinfunction "8_8") (pintype "passive"))
    )
    (net (code "41") (name "/SW5") (class "Default")
      (node (ref "R10") (pin "1") (pinfunction "1_1") (pintype "passive"))
      (node (ref "R9") (pin "1") (pinfunction "1_1") (pintype "passive"))
      (node (ref "SV3") (pin "10") (pinfunction "10_10") (pintype "passive"))
    )
    (net (code "42") (name "/SW6") (class "Default")
      (node (ref "R30") (pin "1") (pinfunction "1_1") (pintype "passive"))
      (node (ref "R31") (pin "1") (pinfunction "1_1") (pintype "passive"))
      (node (ref "SV3") (pin "16") (pinfunction "16_16") (pintype "passive"))
    )
    (net (code "43") (name "/SW7") (class "Default")
      (node (ref "R34") (pin "1") (pinfunction "1_1") (pintype "passive"))
      (node (ref "R35") (pin "1") (pinfunction "1_1") (pintype "passive"))
      (node (ref "SV3") (pin "14") (pinfunction "14_14") (pintype "passive"))
    )
    (net (code "44") (name "/SW8") (class "Default")
      (node (ref "R32") (pin "1") (pinfunction "1_1") (pintype "passive"))
      (node (ref "R33") (pin "1") (pinfunction "1_1") (pintype "passive"))
      (node (ref "SV3") (pin "18") (pinfunction "18_18") (pintype "passive"))
    )
    (net (code "45") (name "/TXD0") (class "Default")
      (node (ref "PCB1") (pin "8") (pinfunction "TXD0/GPIO14_8") (pintype "bidirectional"))
      (node (ref "R53") (pin "2") (pinfunction "2_2") (pintype "passive"))
      (node (ref "R55") (pin "2") (pinfunction "2_2") (pintype "passive"))
    )
    (net (code "46") (name "/TXD0_C") (class "Default")
      (node (ref "R51") (pin "1") (pinfunction "1_1") (pintype "passive"))
      (node (ref "R52") (pin "1") (pinfunction "1_1") (pintype "passive"))
      (node (ref "R53") (pin "1") (pinfunction "1_1") (pintype "passive"))
      (node (ref "SV13") (pin "5") (pinfunction "5_5") (pintype "passive"))
    )
    (net (code "47") (name "/VOL_CLK{slash}D") (class "Default")
      (node (ref "PCB1") (pin "7") (pinfunction "GPIO04/GCKL_7") (pintype "bidirectional"))
      (node (ref "SV7") (pin "2") (pinfunction "2_2") (pintype "passive"))
    )
    (net (code "48") (name "/VOL_I2C_EN") (class "Default")
      (node (ref "PCB1") (pin "32") (pinfunction "GPIO12_32") (pintype "bidirectional"))
      (node (ref "R41") (pin "2") (pinfunction "2_2") (pintype "passive"))
    )
    (net (code "49") (name "/VOL_LR{slash}U") (class "Default")
      (node (ref "PCB1") (pin "36") (pinfunction "GPIO16_36") (pintype "bidirectional"))
      (node (ref "SV7") (pin "4") (pinfunction "4_4") (pintype "passive"))
    )
    (net (code "50") (name "/~{INT}") (class "Default")
      (node (ref "IC3") (pin "20") (pinfunction "INTA_20") (pintype "output"))
      (node (ref "PCB1") (pin "37") (pinfunction "GPIO26_37") (pintype "bidirectional"))
    )
    (net (code "51") (name "/~{SW0}") (class "Default")
      (node (ref "IC1") (pin "8") (pinfunction "O_8") (pintype "output"))
      (node (ref "IC3") (pin "26") (pinfunction "GPA5_26") (pintype "bidirectional"))
    )
    (net (code "52") (name "/~{SW1}") (class "Default")
      (node (ref "IC1") (pin "10") (pinfunction "O_10") (pintype "output"))
      (node (ref "IC3") (pin "25") (pinfunction "GPA4_25") (pintype "bidirectional"))
    )
    (net (code "53") (name "/~{SW2}") (class "Default")
      (node (ref "IC1") (pin "12") (pinfunction "O_12") (pintype "output"))
      (node (ref "IC3") (pin "24") (pinfunction "GPA3_24") (pintype "bidirectional"))
    )
    (net (code "54") (name "/~{SW3}") (class "Default")
      (node (ref "IC1") (pin "6") (pinfunction "O_6") (pintype "output"))
      (node (ref "IC3") (pin "23") (pinfunction "GPA2_23") (pintype "bidirectional"))
    )
    (net (code "55") (name "/~{SW4}") (class "Default")
      (node (ref "IC1") (pin "2") (pinfunction "O_2") (pintype "output"))
      (node (ref "IC3") (pin "22") (pinfunction "GPA1_22") (pintype "bidirectional"))
    )
    (net (code "56") (name "/~{SW5}") (class "Default")
      (node (ref "IC1") (pin "4") (pinfunction "O_4") (pintype "output"))
      (node (ref "IC3") (pin "21") (pinfunction "GPA0_21") (pintype "bidirectional"))
    )
    (net (code "57") (name "/~{SW6}") (class "Default")
      (node (ref "IC2") (pin "4") (pinfunction "O_4") (pintype "output"))
      (node (ref "IC3") (pin "27") (pinfunction "GPA6_27") (pintype "bidirectional"))
    )
    (net (code "58") (name "/~{SW7}") (class "Default")
      (node (ref "IC2") (pin "2") (pinfunction "O_2") (pintype "output"))
      (node (ref "IC3") (pin "28") (pinfunction "GPA7_28") (pintype "bidirectional"))
    )
    (net (code "59") (name "/~{SW8}") (class "Default")
      (node (ref "IC2") (pin "6") (pinfunction "O_6") (pintype "output"))
      (node (ref "PCB1") (pin "31") (pinfunction "GPIO06_31") (pintype "bidirectional"))
    )
    (net (code "60") (name "AGND") (class "Default")
      (node (ref "C1") (pin "2") (pinfunction "2_2") (pintype "passive"))
      (node (ref "C10") (pin "2") (pinfunction "2_2") (pintype "passive"))
      (node (ref "C11") (pin "2") (pinfunction "2_2") (pintype "passive"))
      (node (ref "C12") (pin "2") (pinfunction "2_2") (pintype "passive"))
      (node (ref "C13") (pin "2") (pinfunction "2_2") (pintype "passive"))
      (node (ref "C14") (pin "2") (pinfunction "2_2") (pintype "passive"))
      (node (ref "C15") (pin "2") (pinfunction "2_2") (pintype "passive"))
      (node (ref "C16") (pin "2") (pinfunction "2_2") (pintype "passive"))
      (node (ref "C17") (pin "2") (pinfunction "2_2") (pintype "passive"))
      (node (ref "C18") (pin "2") (pinfunction "2_2") (pintype "passive"))
      (node (ref "C19") (pin "2") (pinfunction "2_2") (pintype "passive"))
      (node (ref "C2") (pin "2") (pinfunction "2_2") (pintype "passive"))
      (node (ref "C20") (pin "2") (pinfunction "2_2") (pintype "passive"))
      (node (ref "C3") (pin "2") (pinfunction "2_2") (pintype "passive"))
      (node (ref "C4") (pin "2") (pinfunction "2_2") (pintype "passive"))
      (node (ref "C5") (pin "2") (pinfunction "2_2") (pintype "passive"))
      (node (ref "C6") (pin "2") (pinfunction "2_2") (pintype "passive"))
      (node (ref "C7") (pin "2") (pinfunction "2_2") (pintype "passive"))
      (node (ref "C8") (pin "2") (pinfunction "2_2") (pintype "passive"))
      (node (ref "C9") (pin "2") (pinfunction "2_2") (pintype "passive"))
      (node (ref "D1") (pin "A") (pinfunction "A_A") (pintype "passive"))
      (node (ref "IC1") (pin "7") (pinfunction "GND_7") (pintype "power_in"))
      (node (ref "IC2") (pin "7") (pinfunction "GND_7") (pintype "power_in"))
      (node (ref "IC3") (pin "10") (pinfunction "VSS_10") (pintype "power_in"))
      (node (ref "PCB1") (pin "14") (pinfunction "GND_14") (pintype "power_in"))
      (node (ref "PCB1") (pin "20") (pinfunction "GND_20") (pintype "power_in"))
      (node (ref "PCB1") (pin "25") (pinfunction "GND_25") (pintype "power_in"))
      (node (ref "PCB1") (pin "30") (pinfunction "GND_30") (pintype "power_in"))
      (node (ref "PCB1") (pin "34") (pinfunction "GND_34") (pintype "power_in"))
      (node (ref "PCB1") (pin "39") (pinfunction "GND_39") (pintype "power_in"))
      (node (ref "PCB1") (pin "6") (pinfunction "GND_6") (pintype "power_in"))
      (node (ref "PCB1") (pin "9") (pinfunction "GND_9") (pintype "power_in"))
      (node (ref "PCB1") (pin "PE_BL") (pinfunction "BL_PE_BL") (pintype "bidirectional"))
      (node (ref "PCB1") (pin "PE_BR") (pinfunction "BR_PE_BR") (pintype "bidirectional"))
      (node (ref "PCB1") (pin "PE_TL") (pinfunction "TL_PE_TL") (pintype "bidirectional"))
      (node (ref "PCB1") (pin "PE_TR") (pinfunction "TR_PE_TR") (pintype "bidirectional"))
      (node (ref "Q7") (pin "2") (pinfunction "E_2") (pintype "passive"))
      (node (ref "R13") (pin "1") (pinfunction "1_1") (pintype "passive"))
      (node (ref "R14") (pin "1") (pinfunction "1_1") (pintype "passive"))
      (node (ref "R15") (pin "1") (pinfunction "1_1") (pintype "passive"))
      (node (ref "R16") (pin "1") (pinfunction "1_1") (pintype "passive"))
      (node (ref "R17") (pin "1") (pinfunction "1_1") (pintype "passive"))
      (node (ref "R18") (pin "1") (pinfunction "1_1") (pintype "passive"))
      (node (ref "R19") (pin "1") (pinfunction "1_1") (pintype "passive"))
      (node (ref "R20") (pin "1") (pinfunction "1_1") (pintype "passive"))
      (node (ref "R22") (pin "2") (pinfunction "2_2") (pintype "passive"))
      (node (ref "R24") (pin "1") (pinfunction "1_1") (pintype "passive"))
      (node (ref "R25") (pin "1") (pinfunction "1_1") (pintype "passive"))
      (node (ref "R26") (pin "1") (pinfunction "1_1") (pintype "passive"))
      (node (ref "R27") (pin "1") (pinfunction "1_1") (pintype "passive"))
      (node (ref "R28") (pin "1") (pinfunction "1_1") (pintype "passive"))
      (node (ref "R36") (pin "1") (pinfunction "1_1") (pintype "passive"))
      (node (ref "R42") (pin "1") (pinfunction "1_1") (pintype "passive"))
      (node (ref "R43") (pin "1") (pinfunction "1_1") (pintype "passive"))
      (node (ref "R44") (pin "1") (pinfunction "1_1") (pintype "passive"))
      (node (ref "R45") (pin "1") (pinfunction "1_1") (pintype "passive"))
      (node (ref "SV1") (pin "1") (pinfunction "1_1") (pintype "passive"))
      (node (ref "SV1") (pin "3") (pinfunction "3_3") (pintype "passive"))
      (node (ref "SV1") (pin "5") (pinfunction "5_5") (pintype "passive"))
      (node (ref "SV10") (pin "1") (pinfunction "1_1") (pintype "passive"))
      (node (ref "SV10") (pin "3") (pinfunction "3_3") (pintype "passive"))
      (node (ref "SV10") (pin "5") (pinfunction "5_5") (pintype "passive"))
      (node (ref "SV11") (pin "3") (pinfunction "3_3") (pintype "passive"))
      (node (ref "SV11") (pin "5") (pinfunction "5_5") (pintype "passive"))
      (node (ref "SV11") (pin "8") (pinfunction "8_8") (pintype "passive"))
      (node (ref "SV13") (pin "1") (pinfunction "1_1") (pintype "passive"))
      (node (ref "SV13") (pin "3") (pinfunction "3_3") (pintype "passive"))
      (node (ref "SV2") (pin "1") (pinfunction "1_1") (pintype "passive"))
      (node (ref "SV2") (pin "3") (pinfunction "3_3") (pintype "passive"))
      (node (ref "SV2") (pin "5") (pinfunction "5_5") (pintype "passive"))
      (node (ref "SV2") (pin "7") (pinfunction "7_7") (pintype "passive"))
      (node (ref "SV2") (pin "9") (pinfunction "9_9") (pintype "passive"))
      (node (ref "SV3") (pin "1") (pinfunction "1_1") (pintype "passive"))
      (node (ref "SV3") (pin "11") (pinfunction "11_11") (pintype "passive"))
      (node (ref "SV3") (pin "13") (pinfunction "13_13") (pintype "passive"))
      (node (ref "SV3") (pin "15") (pinfunction "15_15") (pintype "passive"))
      (node (ref "SV3") (pin "17") (pinfunction "17_17") (pintype "passive"))
      (node (ref "SV3") (pin "3") (pinfunction "3_3") (pintype "passive"))
      (node (ref "SV3") (pin "5") (pinfunction "5_5") (pintype "passive"))
      (node (ref "SV3") (pin "7") (pinfunction "7_7") (pintype "passive"))
      (node (ref "SV3") (pin "9") (pinfunction "9_9") (pintype "passive"))
      (node (ref "SV4") (pin "1") (pinfunction "1_1") (pintype "passive"))
      (node (ref "SV4") (pin "3") (pinfunction "3_3") (pintype "passive"))
      (node (ref "SV4") (pin "5") (pinfunction "5_5") (pintype "passive"))
      (node (ref "SV5") (pin "1") (pinfunction "1_1") (pintype "passive"))
      (node (ref "SV5") (pin "3") (pinfunction "3_3") (pintype "passive"))
      (node (ref "SV5") (pin "5") (pinfunction "5_5") (pintype "passive"))
      (node (ref "SV6") (pin "10") (pinfunction "10_10") (pintype "passive"))
      (node (ref "SV6") (pin "12") (pinfunction "12_12") (pintype "passive"))
      (node (ref "SV6") (pin "13") (pinfunction "13_13") (pintype "passive"))
      (node (ref "SV6") (pin "9") (pinfunction "9_9") (pintype "passive"))
      (node (ref "SV7") (pin "1") (pinfunction "1_1") (pintype "passive"))
      (node (ref "SV7") (pin "3") (pinfunction "3_3") (pintype "passive"))
      (node (ref "SV7") (pin "5") (pinfunction "5_5") (pintype "passive"))
      (node (ref "SV8") (pin "1") (pinfunction "1_1") (pintype "passive"))
      (node (ref "SV8") (pin "3") (pinfunction "3_3") (pintype "passive"))
      (node (ref "SV8") (pin "5") (pinfunction "5_5") (pintype "passive"))
      (node (ref "SV9") (pin "1") (pinfunction "1_1") (pintype "passive"))
      (node (ref "SV9") (pin "3") (pinfunction "3_3") (pintype "passive"))
      (node (ref "X1") (pin "2") (pinfunction "KL_2") (pintype "passive"))
    )
    (net (code "61") (name "Net-(IC1A-I)") (class "Default")
      (node (ref "C4") (pin "1") (pinfunction "1_1") (pintype "passive"))
      (node (ref "IC1") (pin "13") (pinfunction "I_13") (pintype "input"))
      (node (ref "R2") (pin "2") (pinfunction "2_2") (pintype "passive"))
    )
    (net (code "62") (name "Net-(IC1B-I)") (class "Default")
      (node (ref "C5") (pin "1") (pinfunction "1_1") (pintype "passive"))
      (node (ref "IC1") (pin "11") (pinfunction "I_11") (pintype "input"))
      (node (ref "R4") (pin "2") (pinfunction "2_2") (pintype "passive"))
    )
    (net (code "63") (name "Net-(IC1C-I)") (class "Default")
      (node (ref "C6") (pin "1") (pinfunction "1_1") (pintype "passive"))
      (node (ref "IC1") (pin "9") (pinfunction "I_9") (pintype "input"))
      (node (ref "R6") (pin "2") (pinfunction "2_2") (pintype "passive"))
    )
    (net (code "64") (name "Net-(IC1D-I)") (class "Default")
      (node (ref "C7") (pin "1") (pinfunction "1_1") (pintype "passive"))
      (node (ref "IC1") (pin "1") (pinfunction "I_1") (pintype "input"))
      (node (ref "R8") (pin "2") (pinfunction "2_2") (pintype "passive"))
    )
    (net (code "65") (name "Net-(IC1E-I)") (class "Default")
      (node (ref "C8") (pin "1") (pinfunction "1_1") (pintype "passive"))
      (node (ref "IC1") (pin "3") (pinfunction "I_3") (pintype "input"))
      (node (ref "R10") (pin "2") (pinfunction "2_2") (pintype "passive"))
    )
    (net (code "66") (name "Net-(IC1F-I)") (class "Default")
      (node (ref "C9") (pin "1") (pinfunction "1_1") (pintype "passive"))
      (node (ref "IC1") (pin "5") (pinfunction "I_5") (pintype "input"))
      (node (ref "R12") (pin "2") (pinfunction "2_2") (pintype "passive"))
    )
    (net (code "67") (name "Net-(IC2A-I)") (class "Default")
      (node (ref "C19") (pin "1") (pinfunction "1_1") (pintype "passive"))
      (node (ref "IC2") (pin "13") (pinfunction "I_13") (pintype "input"))
      (node (ref "R52") (pin "2") (pinfunction "2_2") (pintype "passive"))
    )
    (net (code "68") (name "Net-(IC2A-O)") (class "Default")
      (node (ref "IC2") (pin "12") (pinfunction "O_12") (pintype "output"))
      (node (ref "R55") (pin "1") (pinfunction "1_1") (pintype "passive"))
    )
    (net (code "69") (name "Net-(IC2B-I)") (class "Default")
      (node (ref "C18") (pin "1") (pinfunction "1_1") (pintype "passive"))
      (node (ref "IC2") (pin "11") (pinfunction "I_11") (pintype "input"))
      (node (ref "R50") (pin "2") (pinfunction "2_2") (pintype "passive"))
    )
    (net (code "70") (name "Net-(IC2B-O)") (class "Default")
      (node (ref "IC2") (pin "10") (pinfunction "O_10") (pintype "output"))
      (node (ref "R56") (pin "1") (pinfunction "1_1") (pintype "passive"))
    )
    (net (code "71") (name "Net-(IC2D-I)") (class "Default")
      (node (ref "C20") (pin "1") (pinfunction "1_1") (pintype "passive"))
      (node (ref "IC2") (pin "1") (pinfunction "I_1") (pintype "input"))
      (node (ref "R35") (pin "2") (pinfunction "2_2") (pintype "passive"))
    )
    (net (code "72") (name "Net-(IC2E-I)") (class "Default")
      (node (ref "C12") (pin "1") (pinfunction "1_1") (pintype "passive"))
      (node (ref "IC2") (pin "3") (pinfunction "I_3") (pintype "input"))
      (node (ref "R31") (pin "2") (pinfunction "2_2") (pintype "passive"))
    )
    (net (code "73") (name "Net-(IC2F-I)") (class "Default")
      (node (ref "C13") (pin "1") (pinfunction "1_1") (pintype "passive"))
      (node (ref "IC2") (pin "5") (pinfunction "I_5") (pintype "input"))
      (node (ref "R33") (pin "2") (pinfunction "2_2") (pintype "passive"))
    )
    (net (code "74") (name "Net-(IC3-~{RESET})") (class "Default")
      (node (ref "IC3") (pin "18") (pinfunction "~{RESET}_18") (pintype "input"))
      (node (ref "R23") (pin "1") (pinfunction "1_1") (pintype "passive"))
    )
    (net (code "75") (name "Net-(K1A-P)") (class "Default")
      (node (ref "K1") (pin "4") (pinfunction "P_4") (pintype "passive"))
      (node (ref "SV11") (pin "2") (pinfunction "2_2") (pintype "passive"))
    )
    (net (code "76") (name "Net-(LED1-PadC)") (class "Default")
      (node (ref "LED1") (pin "C") (pinfunction "C_C") (pintype "passive"))
      (node (ref "R18") (pin "2") (pinfunction "2_2") (pintype "passive"))
    )
    (net (code "77") (name "Net-(LED2-PadC)") (class "Default")
      (node (ref "LED2") (pin "C") (pinfunction "C_C") (pintype "passive"))
      (node (ref "R17") (pin "2") (pinfunction "2_2") (pintype "passive"))
    )
    (net (code "78") (name "Net-(LED3-PadC)") (class "Default")
      (node (ref "LED3") (pin "C") (pinfunction "C_C") (pintype "passive"))
      (node (ref "R16") (pin "2") (pinfunction "2_2") (pintype "passive"))
    )
    (net (code "79") (name "Net-(LED4-PadC)") (class "Default")
      (node (ref "LED4") (pin "C") (pinfunction "C_C") (pintype "passive"))
      (node (ref "R15") (pin "2") (pinfunction "2_2") (pintype "passive"))
    )
    (net (code "80") (name "Net-(LED5-PadC)") (class "Default")
      (node (ref "LED5") (pin "C") (pinfunction "C_C") (pintype "passive"))
      (node (ref "R14") (pin "2") (pinfunction "2_2") (pintype "passive"))
    )
    (net (code "81") (name "Net-(LED6-PadC)") (class "Default")
      (node (ref "LED6") (pin "C") (pinfunction "C_C") (pintype "passive"))
      (node (ref "R13") (pin "2") (pinfunction "2_2") (pintype "passive"))
    )
    (net (code "82") (name "Net-(LED7-PadC)") (class "Default")
      (node (ref "LED7") (pin "C") (pinfunction "C_C") (pintype "passive"))
      (node (ref "R19") (pin "2") (pinfunction "2_2") (pintype "passive"))
    )
    (net (code "83") (name "Net-(LED8-PadC)") (class "Default")
      (node (ref "LED8") (pin "C") (pinfunction "C_C") (pintype "passive"))
      (node (ref "R20") (pin "2") (pinfunction "2_2") (pintype "passive"))
    )
    (net (code "84") (name "Net-(LED9-PadC)") (class "Default")
      (node (ref "LED9") (pin "C") (pinfunction "C_C") (pintype "passive"))
      (node (ref "R36") (pin "2") (pinfunction "2_2") (pintype "passive"))
    )
    (net (code "85") (name "Net-(LED10-PadC)") (class "Default")
      (node (ref "LED10") (pin "C") (pinfunction "C_C") (pintype "passive"))
      (node (ref "R42") (pin "2") (pinfunction "2_2") (pintype "passive"))
    )
    (net (code "86") (name "Net-(LED11-PadC)") (class "Default")
      (node (ref "LED11") (pin "C") (pinfunction "C_C") (pintype "passive"))
      (node (ref "R43") (pin "2") (pinfunction "2_2") (pintype "passive"))
    )
    (net (code "87") (name "Net-(LED12-PadC)") (class "Default")
      (node (ref "LED12") (pin "C") (pinfunction "C_C") (pintype "passive"))
      (node (ref "R24") (pin "2") (pinfunction "2_2") (pintype "passive"))
    )
    (net (code "88") (name "Net-(LED13-PadC)") (class "Default")
      (node (ref "LED13") (pin "C") (pinfunction "C_C") (pintype "passive"))
      (node (ref "R28") (pin "2") (pinfunction "2_2") (pintype "passive"))
    )
    (net (code "89") (name "Net-(Q1-B)") (class "Default")
      (node (ref "Q1") (pin "1") (pinfunction "B_1") (pintype "passive"))
      (node (ref "Q2") (pin "1") (pinfunction "B_1") (pintype "passive"))
      (node (ref "Q3") (pin "1") (pinfunction "B_1") (pintype "passive"))
      (node (ref "Q4") (pin "1") (pinfunction "B_1") (pintype "passive"))
      (node (ref "R41") (pin "1") (pinfunction "1_1") (pintype "passive"))
    )
    (net (code "90") (name "Net-(Q5-D)") (class "Default")
      (node (ref "C16") (pin "1") (pinfunction "1_1") (pintype "passive"))
      (node (ref "F1") (pin "2") (pinfunction "2_2") (pintype "passive"))
      (node (ref "Q5") (pin "3") (pinfunction "D_3") (pintype "passive"))
      (node (ref "Q6") (pin "6") (pinfunction "E_6") (pintype "passive"))
    )
    (net (code "91") (name "Net-(Q5-G)") (class "Default")
      (node (ref "Q5") (pin "1") (pinfunction "G_1") (pintype "passive"))
      (node (ref "Q6") (pin "4") (pinfunction "C_4") (pintype "passive"))
      (node (ref "R45") (pin "2") (pinfunction "2_2") (pintype "passive"))
    )
    (net (code "92") (name "Net-(Q6A-B)") (class "Default")
      (node (ref "Q6") (pin "1") (pinfunction "C_1") (pintype "passive"))
      (node (ref "Q6") (pin "2") (pinfunction "B_2") (pintype "passive"))
      (node (ref "Q6") (pin "3") (pinfunction "B_3") (pintype "passive"))
      (node (ref "R44") (pin "2") (pinfunction "2_2") (pintype "passive"))
    )
    (net (code "93") (name "Net-(Q7-B)") (class "Default")
      (node (ref "Q7") (pin "1") (pinfunction "B_1") (pintype "passive"))
      (node (ref "R21") (pin "1") (pinfunction "1_1") (pintype "passive"))
    )
    (net (code "94") (name "Net-(Q7-C)") (class "Default")
      (node (ref "K1") (pin "2") (pinfunction "2_2") (pintype "passive"))
      (node (ref "Q7") (pin "3") (pinfunction "C_3") (pintype "passive"))
    )
    (net (code "95") (name "Net-(R46-Pad1)") (class "Default")
      (node (ref "R46") (pin "1") (pinfunction "1_1") (pintype "passive"))
      (node (ref "R47") (pin "1") (pinfunction "1_1") (pintype "passive"))
      (node (ref "SV9") (pin "2") (pinfunction "2_2") (pintype "passive"))
    )
    (net (code "96") (name "Net-(R48-Pad2)") (class "Default")
      (node (ref "R48") (pin "2") (pinfunction "2_2") (pintype "passive"))
      (node (ref "R49") (pin "2") (pinfunction "2_2") (pintype "passive"))
      (node (ref "SV9") (pin "5") (pinfunction "5_5") (pintype "passive"))
    )
    (net (code "97") (name "VCC") (class "Default")
      (node (ref "F1") (pin "1") (pinfunction "1_1") (pintype "passive"))
      (node (ref "X1") (pin "1") (pinfunction "KL_1") (pintype "passive"))
    )
    (net (code "98") (name "unconnected-(IC2C-O-Pad8)") (class "Default")
      (node (ref "IC2") (pin "8") (pinfunction "O_8") (pintype "output"))
    )
    (net (code "99") (name "unconnected-(IC3-INTB-Pad19)") (class "Default")
      (node (ref "IC3") (pin "19") (pinfunction "INTB_19") (pintype "output"))
    )
    (net (code "100") (name "unconnected-(K1A-O-Pad3)") (class "Default")
      (node (ref "K1") (pin "3") (pinfunction "O_3") (pintype "passive"))
    )
    (net (code "101") (name "unconnected-(PCB1-GPIO09{slash}MISO-Pad21)") (class "Default")
      (node (ref "PCB1") (pin "21") (pinfunction "GPIO09/MISO_21") (pintype "bidirectional"))
    )
    (net (code "102") (name "unconnected-(PCB1-ID_SC-Pad28)") (class "Default")
      (node (ref "PCB1") (pin "28") (pinfunction "ID_SC_28") (pintype "bidirectional"))
    )
    (net (code "103") (name "unconnected-(PCB1-ID_SD-Pad27)") (class "Default")
      (node (ref "PCB1") (pin "27") (pinfunction "ID_SD_27") (pintype "bidirectional"))
    )
    (net (code "104") (name "unconnected-(SV4-Pad2)") (class "Default")
      (node (ref "SV4") (pin "2") (pinfunction "2_2") (pintype "passive"))
    )
    (net (code "105") (name "unconnected-(SV5-Pad2)") (class "Default")
      (node (ref "SV5") (pin "2") (pinfunction "2_2") (pintype "passive"))
    )
    (net (code "106") (name "unconnected-(SV8-Pad2)") (class "Default")
      (node (ref "SV8") (pin "2") (pinfunction "2_2") (pintype "passive"))
    )
    (net (code "107") (name "unconnected-(SV10-Pad2)") (class "Default")
      (node (ref "SV10") (pin "2") (pinfunction "2_2") (pintype "passive"))
    )
    (net (code "108") (name "unconnected-(SV11-Pad10)") (class "Default")
      (node (ref "SV11") (pin "10") (pinfunction "10_10") (pintype "passive"))
    )
  )
)
